# OpenLog.net
KiCad netlist of a schematic drawn in EAGLE
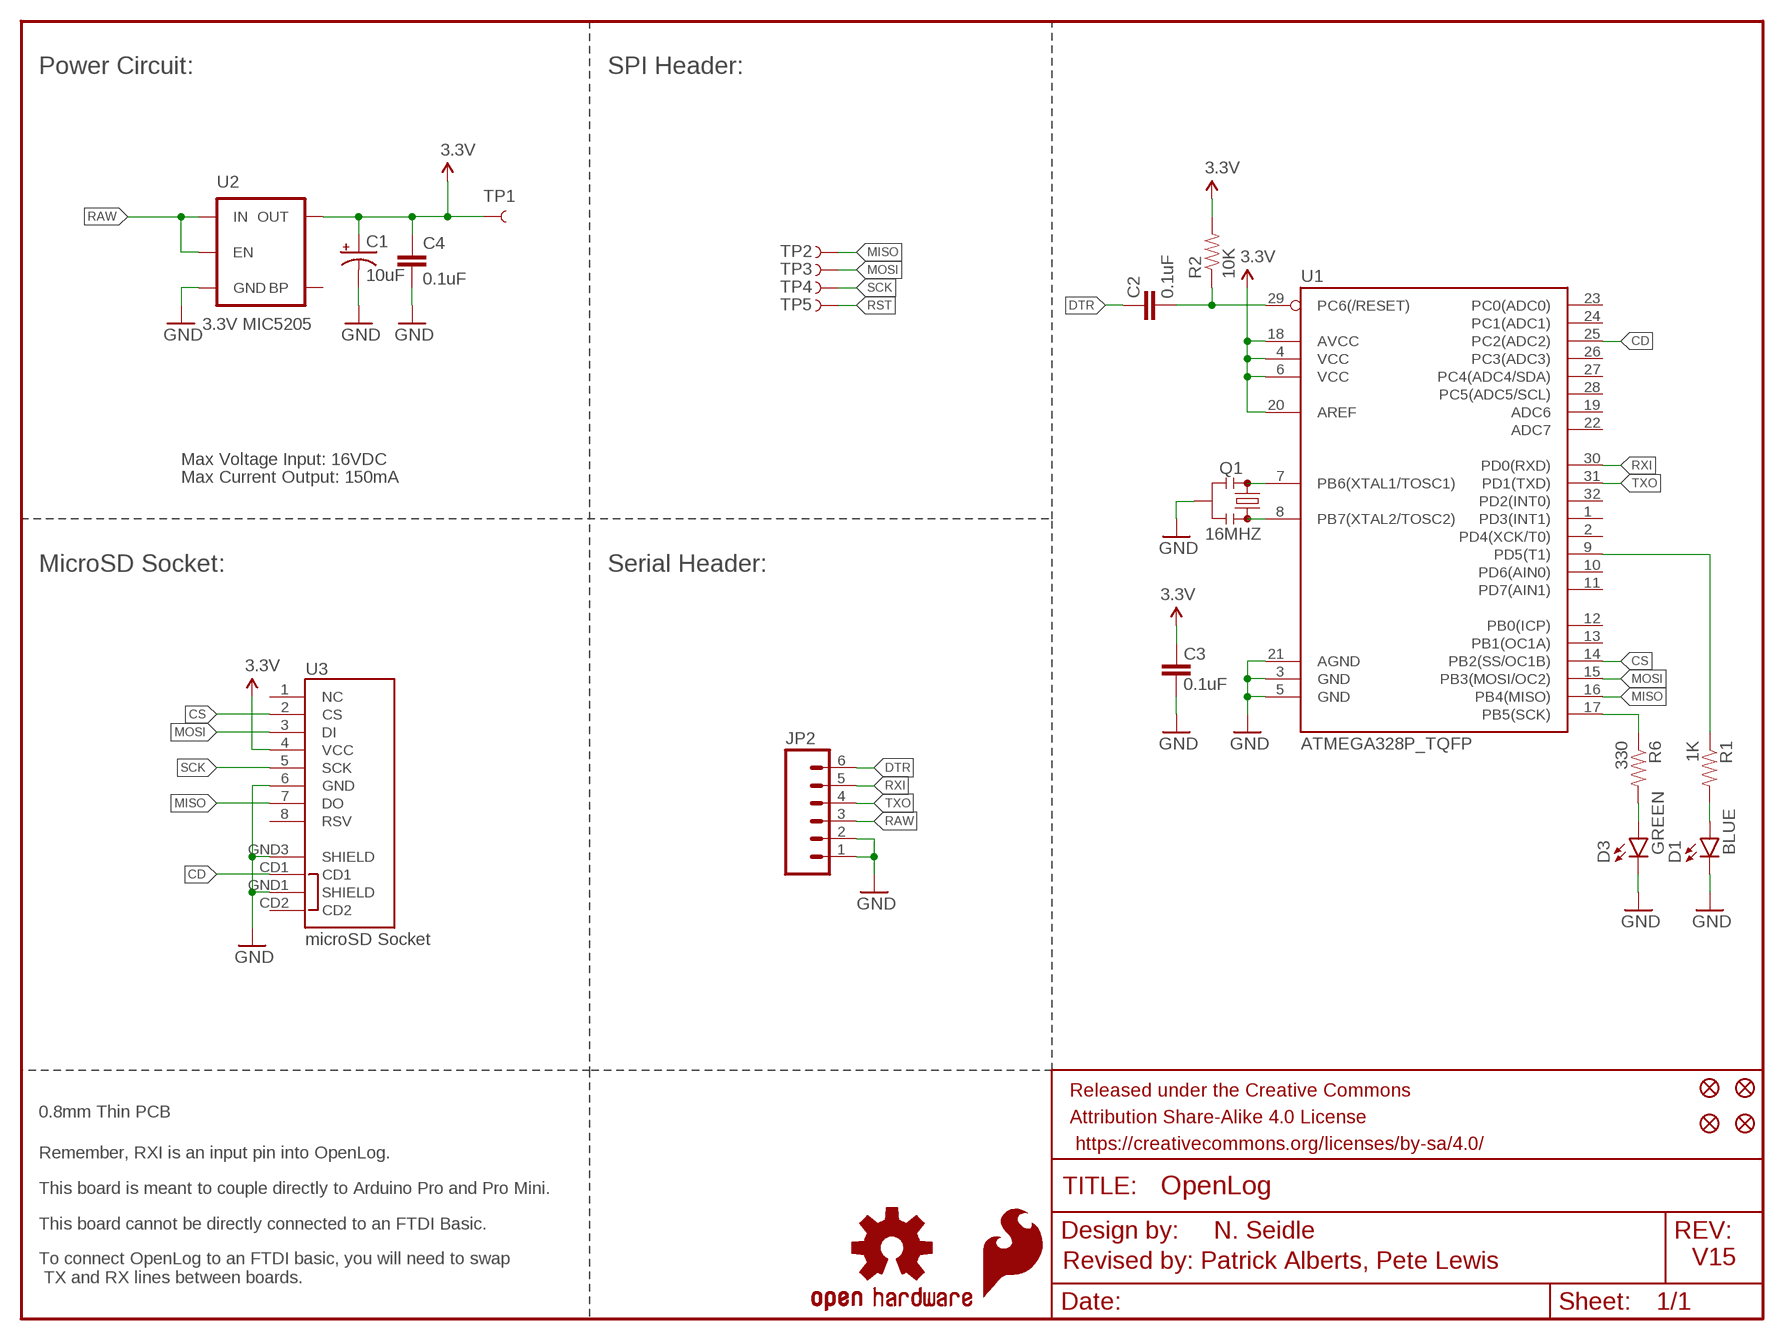
[diagram p0: schematic, sheet 1]

(export (version "E")
  (design (tool "Eeschema 10.0.6"))
  (components
    (comp (ref "C1")
      (value "10uF")
      (footprint "eagle-import:0603-POL")
      (libsource (lib "eagle-import") (part "10UF-6.3V-20%(0603)(TANT){dblquote}"))
    )
    (comp (ref "C2")
      (value "0.1uF")
      (footprint "eagle-import:0603-CAP")
      (libsource (lib "eagle-import") (part "0.1UF-25V(+80/-20%)(0603)"))
    )
    (comp (ref "C3")
      (value "0.1uF")
      (footprint "eagle-import:0603-CAP")
      (libsource (lib "eagle-import") (part "0.1UF-25V(+80/-20%)(0603)"))
    )
    (comp (ref "C4")
      (value "0.1uF")
      (footprint "eagle-import:0603-CAP")
      (libsource (lib "eagle-import") (part "0.1UF-25V(+80/-20%)(0603)"))
    )
    (comp (ref "D1")
      (value "BLUE")
      (footprint "eagle-import:LED-0603")
      (libsource (lib "eagle-import") (part "LED-BLUE0603"))
    )
    (comp (ref "D3")
      (value "GREEN")
      (footprint "eagle-import:LED-0603")
      (libsource (lib "eagle-import") (part "LED-GREEN0603"))
    )
    (comp (ref "FID1")
      (value "FIDUCIALUFIDUCIAL")
      (footprint "eagle-import:MICRO-FIDUCIAL")
      (libsource (lib "eagle-import") (part "FIDUCIALUFIDUCIAL"))
    )
    (comp (ref "FID2")
      (value "FIDUCIALUFIDUCIAL")
      (footprint "eagle-import:MICRO-FIDUCIAL")
      (libsource (lib "eagle-import") (part "FIDUCIALUFIDUCIAL"))
    )
    (comp (ref "FID3")
      (value "FIDUCIALUFIDUCIAL")
      (footprint "eagle-import:MICRO-FIDUCIAL")
      (libsource (lib "eagle-import") (part "FIDUCIALUFIDUCIAL"))
    )
    (comp (ref "FID4")
      (value "FIDUCIALUFIDUCIAL")
      (footprint "eagle-import:MICRO-FIDUCIAL")
      (libsource (lib "eagle-import") (part "FIDUCIALUFIDUCIAL"))
    )
    (comp (ref "FRAME1")
      (value "FRAME-LETTER")
      (footprint "eagle-import:CREATIVE_COMMONS")
      (libsource (lib "eagle-import") (part "FRAME-LETTER"))
    )
    (comp (ref "JP2")
      (value "M06NO_SILK_FEMALE_PTH")
      (footprint "eagle-import:1X06_NO_SILK")
      (libsource (lib "eagle-import") (part "M06NO_SILK_FEMALE_PTH"))
    )
    (comp (ref "LOGO1")
      (value "SFE_LOGO_FLAME.1_INCH")
      (footprint "eagle-import:SFE_LOGO_FLAME_.1")
      (libsource (lib "eagle-import") (part "SFE_LOGO_FLAME.1_INCH"))
    )
    (comp (ref "LOGO2")
      (value "OSHW-LOGOMINI")
      (footprint "eagle-import:OSHW-LOGO-MINI")
      (libsource (lib "eagle-import") (part "OSHW-LOGOMINI"))
    )
    (comp (ref "Q1")
      (value "16MHZ")
      (footprint "eagle-import:RESONATOR-SMD")
      (libsource (lib "eagle-import") (part "RESONATOR16MHZ"))
    )
    (comp (ref "R1")
      (value "1K")
      (footprint "eagle-import:0603-RES")
      (libsource (lib "eagle-import") (part "1KOHM-1/10W-1%(0603)"))
    )
    (comp (ref "R2")
      (value "10K")
      (footprint "eagle-import:0603-RES")
      (libsource (lib "eagle-import") (part "10KOHM-1/10W-1%(0603)0603"))
    )
    (comp (ref "R6")
      (value "330")
      (footprint "eagle-import:0603-RES")
      (libsource (lib "eagle-import") (part "330OHM1/10W1%(0603)"))
    )
    (comp (ref "TP1")
      (value "TEST-POINT3")
      (footprint "eagle-import:PAD.03X.03")
      (libsource (lib "eagle-import") (part "TEST-POINT3"))
    )
    (comp (ref "TP2")
      (value "TEST-POINT3")
      (footprint "eagle-import:PAD.03X.03")
      (libsource (lib "eagle-import") (part "TEST-POINT3"))
    )
    (comp (ref "TP3")
      (value "TEST-POINT3")
      (footprint "eagle-import:PAD.03X.03")
      (libsource (lib "eagle-import") (part "TEST-POINT3"))
    )
    (comp (ref "TP4")
      (value "TEST-POINT3")
      (footprint "eagle-import:PAD.03X.03")
      (libsource (lib "eagle-import") (part "TEST-POINT3"))
    )
    (comp (ref "TP5")
      (value "TEST-POINT3")
      (footprint "eagle-import:PAD.03X.03")
      (libsource (lib "eagle-import") (part "TEST-POINT3"))
    )
    (comp (ref "U1")
      (value "ATMEGA328P_TQFP")
      (footprint "eagle-import:TQFP32-08")
      (libsource (lib "eagle-import") (part "ATMEGA328P_TQFP"))
    )
    (comp (ref "U2")
      (value "3.3V MIC5205")
      (footprint "eagle-import:SOT23-5")
      (libsource (lib "eagle-import") (part "MIC52053.3V"))
    )
    (comp (ref "U3")
      (value "microSD Socket")
      (footprint "eagle-import:MICROSD_1_1")
      (libsource (lib "eagle-import") (part "USD-SOCKET"))
    )
  )
  (nets
    (net (code "1") (name "3.3V") (class "Default")
      (node (ref "C1") (pin "A") (pinfunction "+_A") (pintype "passive"))
      (node (ref "C3") (pin "2") (pinfunction "2_2") (pintype "passive"))
      (node (ref "C4") (pin "1") (pinfunction "1_1") (pintype "passive"))
      (node (ref "R2") (pin "2") (pinfunction "2_2") (pintype "passive"))
      (node (ref "TP1") (pin "P$1") (pinfunction "1_P$1") (pintype "bidirectional"))
      (node (ref "U1") (pin "18") (pinfunction "AVCC_18") (pintype "bidirectional"))
      (node (ref "U1") (pin "20") (pinfunction "AREF_20") (pintype "bidirectional"))
      (node (ref "U1") (pin "4") (pinfunction "VCC_4") (pintype "bidirectional"))
      (node (ref "U1") (pin "6") (pinfunction "VCC_6") (pintype "bidirectional"))
      (node (ref "U2") (pin "5") (pinfunction "OUT_5") (pintype "passive"))
      (node (ref "U3") (pin "4") (pinfunction "VCC_4") (pintype "bidirectional"))
    )
    (net (code "2") (name "CD") (class "Default")
      (node (ref "U1") (pin "25") (pinfunction "PC2(ADC2)_25") (pintype "bidirectional"))
      (node (ref "U3") (pin "CD1") (pinfunction "CD1_CD1") (pintype "bidirectional"))
    )
    (net (code "3") (name "CS") (class "Default")
      (node (ref "U1") (pin "14") (pinfunction "PB2(SS/OC1B)_14") (pintype "bidirectional"))
      (node (ref "U3") (pin "2") (pinfunction "CS_2") (pintype "bidirectional"))
    )
    (net (code "4") (name "DTR") (class "Default")
      (node (ref "C2") (pin "2") (pinfunction "2_2") (pintype "passive"))
      (node (ref "JP2") (pin "6") (pinfunction "6_6") (pintype "passive"))
    )
    (net (code "5") (name "GND") (class "Default")
      (node (ref "C1") (pin "K") (pinfunction "-_K") (pintype "passive"))
      (node (ref "C3") (pin "1") (pinfunction "1_1") (pintype "passive"))
      (node (ref "C4") (pin "2") (pinfunction "2_2") (pintype "passive"))
      (node (ref "D1") (pin "C") (pinfunction "C_C") (pintype "passive"))
      (node (ref "D3") (pin "C") (pinfunction "C_C") (pintype "passive"))
      (node (ref "JP2") (pin "1") (pinfunction "1_1") (pintype "passive"))
      (node (ref "JP2") (pin "2") (pinfunction "2_2") (pintype "passive"))
      (node (ref "Q1") (pin "2") (pinfunction "2_2") (pintype "passive"))
      (node (ref "U1") (pin "21") (pinfunction "AGND_21") (pintype "bidirectional"))
      (node (ref "U1") (pin "3") (pinfunction "GND_3") (pintype "bidirectional"))
      (node (ref "U1") (pin "5") (pinfunction "GND_5") (pintype "bidirectional"))
      (node (ref "U2") (pin "2") (pinfunction "GND_2") (pintype "input"))
      (node (ref "U3") (pin "6") (pinfunction "GND_6") (pintype "bidirectional"))
      (node (ref "U3") (pin "GND1") (pinfunction "SHIELD_GND1") (pintype "bidirectional"))
      (node (ref "U3") (pin "GND3") (pinfunction "SHIELD_GND3") (pintype "bidirectional"))
    )
    (net (code "6") (name "MISO") (class "Default")
      (node (ref "TP2") (pin "P$1") (pinfunction "1_P$1") (pintype "bidirectional"))
      (node (ref "U1") (pin "16") (pinfunction "PB4(MISO)_16") (pintype "bidirectional"))
      (node (ref "U3") (pin "7") (pinfunction "DO_7") (pintype "bidirectional"))
    )
    (net (code "7") (name "MOSI") (class "Default")
      (node (ref "TP3") (pin "P$1") (pinfunction "1_P$1") (pintype "bidirectional"))
      (node (ref "U1") (pin "15") (pinfunction "PB3(MOSI/OC2)_15") (pintype "bidirectional"))
      (node (ref "U3") (pin "3") (pinfunction "DI_3") (pintype "bidirectional"))
    )
    (net (code "8") (name "Net-(D1-PadA)") (class "Default")
      (node (ref "D1") (pin "A") (pinfunction "A_A") (pintype "passive"))
      (node (ref "R1") (pin "2") (pinfunction "2_2") (pintype "passive"))
    )
    (net (code "9") (name "Net-(D3-PadA)") (class "Default")
      (node (ref "D3") (pin "A") (pinfunction "A_A") (pintype "passive"))
      (node (ref "R6") (pin "2") (pinfunction "2_2") (pintype "passive"))
    )
    (net (code "10") (name "Net-(U1-PB6(XTAL1{slash}TOSC1))") (class "Default")
      (node (ref "Q1") (pin "3") (pinfunction "3_3") (pintype "passive"))
      (node (ref "U1") (pin "7") (pinfunction "PB6(XTAL1/TOSC1)_7") (pintype "bidirectional"))
    )
    (net (code "11") (name "Net-(U1-PB7(XTAL2{slash}TOSC2))") (class "Default")
      (node (ref "Q1") (pin "1") (pinfunction "1_1") (pintype "passive"))
      (node (ref "U1") (pin "8") (pinfunction "PB7(XTAL2/TOSC2)_8") (pintype "bidirectional"))
    )
    (net (code "12") (name "Net-(U1-PD5(T1))") (class "Default")
      (node (ref "R1") (pin "1") (pinfunction "1_1") (pintype "passive"))
      (node (ref "U1") (pin "9") (pinfunction "PD5(T1)_9") (pintype "bidirectional"))
    )
    (net (code "13") (name "RAW") (class "Default")
      (node (ref "JP2") (pin "3") (pinfunction "3_3") (pintype "passive"))
      (node (ref "U2") (pin "1") (pinfunction "IN_1") (pintype "input"))
      (node (ref "U2") (pin "3") (pinfunction "EN_3") (pintype "input"))
    )
    (net (code "14") (name "RST") (class "Default")
      (node (ref "C2") (pin "1") (pinfunction "1_1") (pintype "passive"))
      (node (ref "R2") (pin "1") (pinfunction "1_1") (pintype "passive"))
      (node (ref "TP5") (pin "P$1") (pinfunction "1_P$1") (pintype "bidirectional"))
      (node (ref "U1") (pin "29") (pinfunction "PC6(/RESET)_29") (pintype "bidirectional"))
    )
    (net (code "15") (name "RXI") (class "Default")
      (node (ref "JP2") (pin "5") (pinfunction "5_5") (pintype "passive"))
      (node (ref "U1") (pin "30") (pinfunction "PD0(RXD)_30") (pintype "bidirectional"))
    )
    (net (code "16") (name "SCK") (class "Default")
      (node (ref "R6") (pin "1") (pinfunction "1_1") (pintype "passive"))
      (node (ref "TP4") (pin "P$1") (pinfunction "1_P$1") (pintype "bidirectional"))
      (node (ref "U1") (pin "17") (pinfunction "PB5(SCK)_17") (pintype "bidirectional"))
      (node (ref "U3") (pin "5") (pinfunction "SCK_5") (pintype "bidirectional"))
    )
    (net (code "17") (name "TXO") (class "Default")
      (node (ref "JP2") (pin "4") (pinfunction "4_4") (pintype "passive"))
      (node (ref "U1") (pin "31") (pinfunction "PD1(TXD)_31") (pintype "bidirectional"))
    )
    (net (code "18") (name "unconnected-(U1-ADC6-Pad19)") (class "Default")
      (node (ref "U1") (pin "19") (pinfunction "ADC6_19") (pintype "bidirectional"))
    )
    (net (code "19") (name "unconnected-(U1-ADC7-Pad22)") (class "Default")
      (node (ref "U1") (pin "22") (pinfunction "ADC7_22") (pintype "bidirectional"))
    )
    (net (code "20") (name "unconnected-(U1-PB0(ICP)-Pad12)") (class "Default")
      (node (ref "U1") (pin "12") (pinfunction "PB0(ICP)_12") (pintype "bidirectional"))
    )
    (net (code "21") (name "unconnected-(U1-PB1(OC1A)-Pad13)") (class "Default")
      (node (ref "U1") (pin "13") (pinfunction "PB1(OC1A)_13") (pintype "bidirectional"))
    )
    (net (code "22") (name "unconnected-(U1-PC0(ADC0)-Pad23)") (class "Default")
      (node (ref "U1") (pin "23") (pinfunction "PC0(ADC0)_23") (pintype "bidirectional"))
    )
    (net (code "23") (name "unconnected-(U1-PC1(ADC1)-Pad24)") (class "Default")
      (node (ref "U1") (pin "24") (pinfunction "PC1(ADC1)_24") (pintype "bidirectional"))
    )
    (net (code "24") (name "unconnected-(U1-PC3(ADC3)-Pad26)") (class "Default")
      (node (ref "U1") (pin "26") (pinfunction "PC3(ADC3)_26") (pintype "bidirectional"))
    )
    (net (code "25") (name "unconnected-(U1-PC4(ADC4{slash}SDA)-Pad27)") (class "Default")
      (node (ref "U1") (pin "27") (pinfunction "PC4(ADC4/SDA)_27") (pintype "bidirectional"))
    )
    (net (code "26") (name "unconnected-(U1-PC5(ADC5{slash}SCL)-Pad28)") (class "Default")
      (node (ref "U1") (pin "28") (pinfunction "PC5(ADC5/SCL)_28") (pintype "bidirectional"))
    )
    (net (code "27") (name "unconnected-(U1-PD2(INT0)-Pad32)") (class "Default")
      (node (ref "U1") (pin "32") (pinfunction "PD2(INT0)_32") (pintype "bidirectional"))
    )
    (net (code "28") (name "unconnected-(U1-PD3(INT1)-Pad1)") (class "Default")
      (node (ref "U1") (pin "1") (pinfunction "PD3(INT1)_1") (pintype "bidirectional"))
    )
    (net (code "29") (name "unconnected-(U1-PD4(XCK{slash}T0)-Pad2)") (class "Default")
      (node (ref "U1") (pin "2") (pinfunction "PD4(XCK/T0)_2") (pintype "bidirectional"))
    )
    (net (code "30") (name "unconnected-(U1-PD6(AIN0)-Pad10)") (class "Default")
      (node (ref "U1") (pin "10") (pinfunction "PD6(AIN0)_10") (pintype "bidirectional"))
    )
    (net (code "31") (name "unconnected-(U1-PD7(AIN1)-Pad11)") (class "Default")
      (node (ref "U1") (pin "11") (pinfunction "PD7(AIN1)_11") (pintype "bidirectional"))
    )
    (net (code "32") (name "unconnected-(U2-BP-Pad4)") (class "Default")
      (node (ref "U2") (pin "4") (pinfunction "BP_4") (pintype "input"))
    )
    (net (code "33") (name "unconnected-(U3-NC-Pad1)") (class "Default")
      (node (ref "U3") (pin "1") (pinfunction "NC_1") (pintype "bidirectional"))
    )
    (net (code "34") (name "unconnected-(U3-PadCD2)") (class "Default")
      (node (ref "U3") (pin "CD2") (pinfunction "CD2_CD2") (pintype "bidirectional"))
    )
    (net (code "35") (name "unconnected-(U3-RSV-Pad8)") (class "Default")
      (node (ref "U3") (pin "8") (pinfunction "RSV_8") (pintype "bidirectional"))
    )
  )
)
